# Sensors.net
KiCad netlist of a schematic drawn in Altium Designer
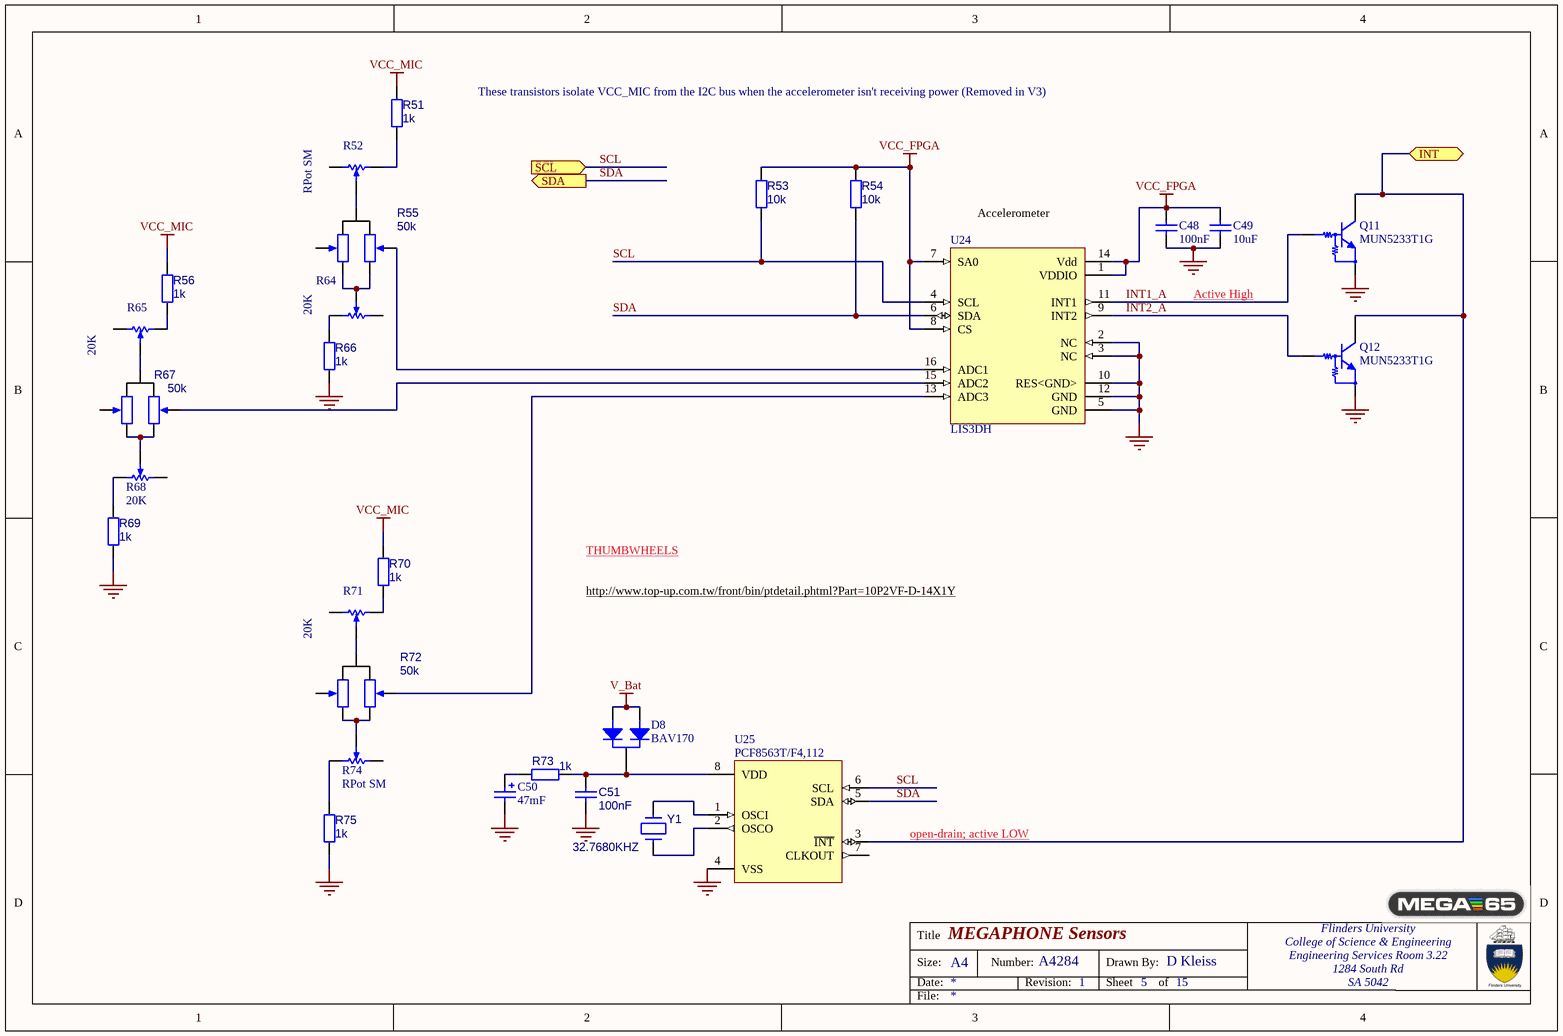
[diagram p0: Sensors.SchDoc]

(export (version "E")
  (design (tool "Eeschema 10.0.6"))
  (components
    (comp (ref "C48")
      (value "100nF")
      (footprint "CAPC0805(2012)100_N")
      (description "0805 (2012 Metric)")
      (fields (field (name "TOLERANCE") "Â±2%"))
      (libsource (lib "Altium Content Vault") (part "CMP-1036-01531-1"))
    )
    (comp (ref "C49")
      (value "10uF")
      (footprint "CAPC0805(2012)100_N")
      (description "0805 (2012 Metric)")
      (fields (field (name "TOLERANCE") "Â±2%"))
      (libsource (lib "MEGAphone") (part "CMP-1036-01531-1"))
    )
    (comp (ref "C50")
      (value "47mF")
      (footprint "CAP SMD 10.5D 5.5H")
      (description "Polarized Capacitor (Radial)")
      (fields (field (name "MANUFACTURER") "KEMET"))
      (libsource (lib "Workshop Library 2010_06_24") (part "Cap Pol"))
    )
    (comp (ref "C51")
      (value "100nF")
      (footprint "0603_CAP UF HD")
      (description "Capacitor")
      (libsource (lib "Workshop Library 2010_06_24") (part "Cap"))
    )
    (comp (ref "D8")
      (value "BAV170")
      (footprint "SOT-23")
      (description "Dual Common Cathode Silicon Low Leakage Diode 3-Pin SOT-23")
      (fields (field (name "MANUFACTURER") "Infineon Technologies"))
      (libsource (lib "Workshop Library 2010_06_24") (part "BAV170"))
    )
    (comp (ref "Q11")
      (value "MUN5233T1G")
      (footprint "SC70-3 (SOT-323)")
      (description "NPN Bipolar Transistor, Prebiased")
      (fields (field (name "MANUFACTURER") "ON Semiconductor"))
      (libsource (lib "Workshop Library 2010_06_24") (part "Transistor NPN Prebiased"))
    )
    (comp (ref "Q12")
      (value "MUN5233T1G")
      (footprint "SC70-3 (SOT-323)")
      (description "NPN Bipolar Transistor, Prebiased")
      (fields (field (name "MANUFACTURER") "ON Semiconductor"))
      (libsource (lib "Workshop Library 2010_06_24") (part "Transistor NPN Prebiased"))
    )
    (comp (ref "R51")
      (value "1k")
      (footprint "0603-RESISTOR HD")
      (description "Resistor")
      (libsource (lib "MEGAphone") (part "Resistor"))
    )
    (comp (ref "R52")
      (value "RPot SM")
      (footprint "POT4MM-2")
      (description "Square Trimming Potentiometer")
      (fields (field (name "PUBLISHER") "Altium Limited"))
      (libsource (lib "Miscellaneous Devices") (part "RPot SM"))
    )
    (comp (ref "R53")
      (value "10k")
      (footprint "0603-RESISTOR HD")
      (description "Resistor")
      (libsource (lib "MEGAphone") (part "Resistor"))
    )
    (comp (ref "R54")
      (value "10k")
      (footprint "0603-RESISTOR HD")
      (description "Resistor")
      (libsource (lib "MEGAphone") (part "Resistor"))
    )
    (comp (ref "R55")
      (value "50k")
      (footprint "POT 10P2VF-D-141Y")
      (description "Resistor")
      (fields (field (name "MANUFACTURER") "TOP UP Industry"))
      (libsource (lib "Workshop Library 2010_06_24") (part "Resistor Potentiometer Dual"))
    )
    (comp (ref "R56")
      (value "1k")
      (footprint "0603-RESISTOR HD")
      (description "Resistor")
      (libsource (lib "MEGAphone") (part "Resistor"))
    )
    (comp (ref "R64")
      (value "20K")
      (footprint "POT4MM-2")
      (description "Square Trimming Potentiometer")
      (fields (field (name "PUBLISHER") "Altium Limited"))
      (libsource (lib "Miscellaneous Devices") (part "RPot SM"))
    )
    (comp (ref "R65")
      (value "20K")
      (footprint "POT4MM-2")
      (description "Square Trimming Potentiometer")
      (fields (field (name "PUBLISHER") "Altium Limited"))
      (libsource (lib "Miscellaneous Devices") (part "RPot SM"))
    )
    (comp (ref "R66")
      (value "1k")
      (footprint "0603-RESISTOR HD")
      (description "Resistor")
      (libsource (lib "MEGAphone") (part "Resistor"))
    )
    (comp (ref "R67")
      (value "50k")
      (footprint "POT 10P2VF-D-141Y")
      (description "Resistor")
      (fields (field (name "MANUFACTURER") "TOP UP Industry"))
      (libsource (lib "Workshop Library 2010_06_24") (part "Resistor Potentiometer Dual"))
    )
    (comp (ref "R68")
      (value "20K")
      (footprint "POT4MM-2")
      (description "Square Trimming Potentiometer")
      (fields (field (name "PUBLISHER") "Altium Limited"))
      (libsource (lib "Miscellaneous Devices") (part "RPot SM"))
    )
    (comp (ref "R69")
      (value "1k")
      (footprint "0603-RESISTOR HD")
      (description "Resistor")
      (libsource (lib "MEGAphone") (part "Resistor"))
    )
    (comp (ref "R70")
      (value "1k")
      (footprint "0603-RESISTOR HD")
      (description "Resistor")
      (libsource (lib "MEGAphone") (part "Resistor"))
    )
    (comp (ref "R71")
      (value "20K")
      (footprint "POT4MM-2")
      (description "Square Trimming Potentiometer")
      (fields (field (name "PUBLISHER") "Altium Limited"))
      (libsource (lib "Miscellaneous Devices") (part "RPot SM"))
    )
    (comp (ref "R72")
      (value "50k")
      (footprint "POT 10P2VF-D-141Y")
      (description "Resistor")
      (fields (field (name "MANUFACTURER") "TOP UP Industry"))
      (libsource (lib "Workshop Library 2010_06_24") (part "Resistor Potentiometer Dual"))
    )
    (comp (ref "R73")
      (value "1k")
      (footprint "0603-RESISTOR HD")
      (description "Resistor")
      (libsource (lib "Workshop Library 2010_06_24") (part "Resistor"))
    )
    (comp (ref "R74")
      (value "RPot SM")
      (footprint "POT4MM-2")
      (description "Square Trimming Potentiometer")
      (fields (field (name "PUBLISHER") "Altium Limited"))
      (libsource (lib "Miscellaneous Devices") (part "RPot SM"))
    )
    (comp (ref "R75")
      (value "1k")
      (footprint "0603-RESISTOR HD")
      (description "Resistor")
      (libsource (lib "MEGAphone") (part "Resistor"))
    )
    (comp (ref "U24")
      (value "LIS3DH")
      (footprint "LGA-16_3x3x1mm")
      (description "Accelerometer")
      (libsource (lib "MegaPhone") (part "LIS3DH"))
    )
    (comp (ref "U25")
      (value "PCF8563T/F4,112")
      (footprint "SOIC-8-H_SLDR")
      (description "PCF8563 Series 1.8 - 5.5 V 250 mA Real-time Clock/Calendar - SOIC-8")
      (libsource (lib "Workshop Library 2010_06_24") (part "PCF8563T/F4,112"))
    )
    (comp (ref "Y1")
      (value "32.7680KHZ")
      (footprint "FC-135")
      (description "Crystal")
      (fields (field (name "MANUFACTURER") "EPSON"))
      (libsource (lib "Workshop Library 2010_06_24") (part "CRYSTAL"))
    )
  )
  (nets
    (net (code "1") (name "/INT") (class "Default")
      (node (ref "Q11") (pin "3") (pinfunction "C_3") (pintype "passive"))
      (node (ref "Q12") (pin "3") (pinfunction "C_3") (pintype "passive"))
      (node (ref "U25") (pin "3") (pinfunction "~{INT}_3") (pintype "bidirectional"))
    )
    (net (code "2") (name "/INT1_A") (class "Default")
      (node (ref "Q11") (pin "2") (pinfunction "B_2") (pintype "passive"))
      (node (ref "U24") (pin "11") (pinfunction "INT1_11") (pintype "output"))
    )
    (net (code "3") (name "/INT2_A") (class "Default")
      (node (ref "Q12") (pin "2") (pinfunction "B_2") (pintype "passive"))
      (node (ref "U24") (pin "9") (pinfunction "INT2_9") (pintype "output"))
    )
    (net (code "4") (name "/SCL") (class "Default")
      (node (ref "R53") (pin "2") (pinfunction "2_2") (pintype "passive"))
      (node (ref "U24") (pin "4") (pinfunction "SCL_4") (pintype "input"))
      (node (ref "U25") (pin "6") (pinfunction "SCL_6") (pintype "input"))
    )
    (net (code "5") (name "/SDA") (class "Default")
      (node (ref "R54") (pin "2") (pinfunction "2_2") (pintype "passive"))
      (node (ref "U24") (pin "6") (pinfunction "SDA_6") (pintype "bidirectional"))
      (node (ref "U25") (pin "5") (pinfunction "SDA_5") (pintype "bidirectional"))
    )
    (net (code "6") (name "GND") (class "Default")
      (node (ref "C48") (pin "2") (pinfunction "2_2") (pintype "passive"))
      (node (ref "C49") (pin "2") (pinfunction "2_2") (pintype "passive"))
      (node (ref "C50") (pin "2") (pinfunction "2_2") (pintype "passive"))
      (node (ref "C51") (pin "2") (pinfunction "2_2") (pintype "passive"))
      (node (ref "Q11") (pin "1") (pinfunction "E_1") (pintype "passive"))
      (node (ref "Q12") (pin "1") (pinfunction "E_1") (pintype "passive"))
      (node (ref "R66") (pin "2") (pinfunction "2_2") (pintype "passive"))
      (node (ref "R69") (pin "2") (pinfunction "2_2") (pintype "passive"))
      (node (ref "R75") (pin "2") (pinfunction "2_2") (pintype "passive"))
      (node (ref "U24") (pin "10") (pinfunction "RES<GND>_10") (pintype "power_in"))
      (node (ref "U24") (pin "12") (pinfunction "GND_12") (pintype "passive"))
      (node (ref "U24") (pin "2") (pinfunction "NC_2") (pintype "input"))
      (node (ref "U24") (pin "3") (pinfunction "NC_3") (pintype "input"))
      (node (ref "U24") (pin "5") (pinfunction "GND_5") (pintype "passive"))
      (node (ref "U25") (pin "4") (pinfunction "VSS_4") (pintype "passive"))
    )
    (net (code "7") (name "Net-(C50-Pad1)") (class "Default")
      (node (ref "C50") (pin "1") (pinfunction "1_1") (pintype "passive"))
      (node (ref "R73") (pin "2") (pinfunction "2_2") (pintype "passive"))
    )
    (net (code "8") (name "Net-(D8-K)") (class "Default")
      (node (ref "C51") (pin "1") (pinfunction "1_1") (pintype "passive"))
      (node (ref "D8") (pin "3") (pinfunction "K_3") (pintype "passive"))
      (node (ref "R73") (pin "1") (pinfunction "1_1") (pintype "passive"))
      (node (ref "U25") (pin "8") (pinfunction "VDD_8") (pintype "power_in"))
    )
    (net (code "9") (name "Net-(R52-+)") (class "Default")
      (node (ref "R51") (pin "2") (pinfunction "2_2") (pintype "passive"))
      (node (ref "R52") (pin "CW") (pinfunction "+_CW") (pintype "passive"))
    )
    (net (code "10") (name "Net-(R52-PadW)") (class "Default")
      (node (ref "R52") (pin "W") (pinfunction "W_W") (pintype "passive"))
      (node (ref "R55") (pin "1") (pinfunction "1_1") (pintype "passive"))
    )
    (net (code "11") (name "Net-(R55-Pad3A)") (class "Default")
      (node (ref "R55") (pin "3A") (pinfunction "3A_3A") (pintype "passive"))
      (node (ref "R55") (pin "3B") (pinfunction "3B_3B") (pintype "passive"))
      (node (ref "R64") (pin "W") (pinfunction "W_W") (pintype "passive"))
    )
    (net (code "12") (name "Net-(R64-+)") (class "Default")
      (node (ref "R64") (pin "CW") (pinfunction "+_CW") (pintype "passive"))
      (node (ref "R66") (pin "1") (pinfunction "1_1") (pintype "passive"))
    )
    (net (code "13") (name "Net-(R65-+)") (class "Default")
      (node (ref "R56") (pin "2") (pinfunction "2_2") (pintype "passive"))
      (node (ref "R65") (pin "CW") (pinfunction "+_CW") (pintype "passive"))
    )
    (net (code "14") (name "Net-(R65-PadW)") (class "Default")
      (node (ref "R65") (pin "W") (pinfunction "W_W") (pintype "passive"))
      (node (ref "R67") (pin "1") (pinfunction "1_1") (pintype "passive"))
    )
    (net (code "15") (name "Net-(R67-Pad3A)") (class "Default")
      (node (ref "R67") (pin "3A") (pinfunction "3A_3A") (pintype "passive"))
      (node (ref "R67") (pin "3B") (pinfunction "3B_3B") (pintype "passive"))
      (node (ref "R68") (pin "W") (pinfunction "W_W") (pintype "passive"))
    )
    (net (code "16") (name "Net-(R68-+)") (class "Default")
      (node (ref "R68") (pin "CW") (pinfunction "+_CW") (pintype "passive"))
      (node (ref "R69") (pin "1") (pinfunction "1_1") (pintype "passive"))
    )
    (net (code "17") (name "Net-(R71-+)") (class "Default")
      (node (ref "R70") (pin "2") (pinfunction "2_2") (pintype "passive"))
      (node (ref "R71") (pin "CW") (pinfunction "+_CW") (pintype "passive"))
    )
    (net (code "18") (name "Net-(R71-PadW)") (class "Default")
      (node (ref "R71") (pin "W") (pinfunction "W_W") (pintype "passive"))
      (node (ref "R72") (pin "1") (pinfunction "1_1") (pintype "passive"))
    )
    (net (code "19") (name "Net-(R72-Pad3A)") (class "Default")
      (node (ref "R72") (pin "3A") (pinfunction "3A_3A") (pintype "passive"))
      (node (ref "R72") (pin "3B") (pinfunction "3B_3B") (pintype "passive"))
      (node (ref "R74") (pin "W") (pinfunction "W_W") (pintype "passive"))
    )
    (net (code "20") (name "Net-(R74-+)") (class "Default")
      (node (ref "R74") (pin "CW") (pinfunction "+_CW") (pintype "passive"))
      (node (ref "R75") (pin "1") (pinfunction "1_1") (pintype "passive"))
    )
    (net (code "21") (name "Net-(U24-ADC1)") (class "Default")
      (node (ref "R55") (pin "2A") (pinfunction "2A_2A") (pintype "passive"))
      (node (ref "U24") (pin "16") (pinfunction "ADC1_16") (pintype "input"))
    )
    (net (code "22") (name "Net-(U24-ADC2)") (class "Default")
      (node (ref "R67") (pin "2A") (pinfunction "2A_2A") (pintype "passive"))
      (node (ref "U24") (pin "15") (pinfunction "ADC2_15") (pintype "input"))
    )
    (net (code "23") (name "Net-(U24-ADC3)") (class "Default")
      (node (ref "R72") (pin "2A") (pinfunction "2A_2A") (pintype "passive"))
      (node (ref "U24") (pin "13") (pinfunction "ADC3_13") (pintype "input"))
    )
    (net (code "24") (name "Net-(U25-OSCI)") (class "Default")
      (node (ref "U25") (pin "1") (pinfunction "OSCI_1") (pintype "input"))
      (node (ref "Y1") (pin "2") (pintype "passive"))
    )
    (net (code "25") (name "Net-(U25-OSCO)") (class "Default")
      (node (ref "U25") (pin "2") (pinfunction "OSCO_2") (pintype "output"))
      (node (ref "Y1") (pin "1") (pintype "passive"))
    )
    (net (code "26") (name "VCC_FPGA") (class "Default")
      (node (ref "C48") (pin "1") (pinfunction "1_1") (pintype "passive"))
      (node (ref "C49") (pin "1") (pinfunction "1_1") (pintype "passive"))
      (node (ref "R53") (pin "1") (pinfunction "1_1") (pintype "passive"))
      (node (ref "R54") (pin "1") (pinfunction "1_1") (pintype "passive"))
      (node (ref "U24") (pin "1") (pinfunction "VDDIO_1") (pintype "power_in"))
      (node (ref "U24") (pin "14") (pinfunction "Vdd_14") (pintype "power_in"))
      (node (ref "U24") (pin "7") (pinfunction "SA0_7") (pintype "input"))
      (node (ref "U24") (pin "8") (pinfunction "CS_8") (pintype "input"))
    )
    (net (code "27") (name "VCC_MIC") (class "Default")
      (node (ref "R51") (pin "1") (pinfunction "1_1") (pintype "passive"))
      (node (ref "R56") (pin "1") (pinfunction "1_1") (pintype "passive"))
      (node (ref "R70") (pin "1") (pinfunction "1_1") (pintype "passive"))
    )
    (net (code "28") (name "V_Bat") (class "Default")
      (node (ref "D8") (pin "1") (pinfunction "A1_1") (pintype "passive"))
      (node (ref "D8") (pin "2") (pinfunction "A2_2") (pintype "passive"))
    )
    (net (code "29") (name "unconnected-(R52---PadCCW)") (class "Default")
      (node (ref "R52") (pin "CCW") (pinfunction "-_CCW") (pintype "passive"))
    )
    (net (code "30") (name "unconnected-(R55-Pad2B)") (class "Default")
      (node (ref "R55") (pin "2B") (pinfunction "2B_2B") (pintype "passive"))
    )
    (net (code "31") (name "unconnected-(R64---PadCCW)") (class "Default")
      (node (ref "R64") (pin "CCW") (pinfunction "-_CCW") (pintype "passive"))
    )
    (net (code "32") (name "unconnected-(R65---PadCCW)") (class "Default")
      (node (ref "R65") (pin "CCW") (pinfunction "-_CCW") (pintype "passive"))
    )
    (net (code "33") (name "unconnected-(R67-Pad2B)") (class "Default")
      (node (ref "R67") (pin "2B") (pinfunction "2B_2B") (pintype "passive"))
    )
    (net (code "34") (name "unconnected-(R68---PadCCW)") (class "Default")
      (node (ref "R68") (pin "CCW") (pinfunction "-_CCW") (pintype "passive"))
    )
    (net (code "35") (name "unconnected-(R71---PadCCW)") (class "Default")
      (node (ref "R71") (pin "CCW") (pinfunction "-_CCW") (pintype "passive"))
    )
    (net (code "36") (name "unconnected-(R72-Pad2B)") (class "Default")
      (node (ref "R72") (pin "2B") (pinfunction "2B_2B") (pintype "passive"))
    )
    (net (code "37") (name "unconnected-(R74---PadCCW)") (class "Default")
      (node (ref "R74") (pin "CCW") (pinfunction "-_CCW") (pintype "passive"))
    )
    (net (code "38") (name "unconnected-(U25-CLKOUT-Pad7)") (class "Default")
      (node (ref "U25") (pin "7") (pinfunction "CLKOUT_7") (pintype "output"))
    )
  )
)
